# Nudge.net
KiCad netlist of a schematic drawn in EasyEDA Pro
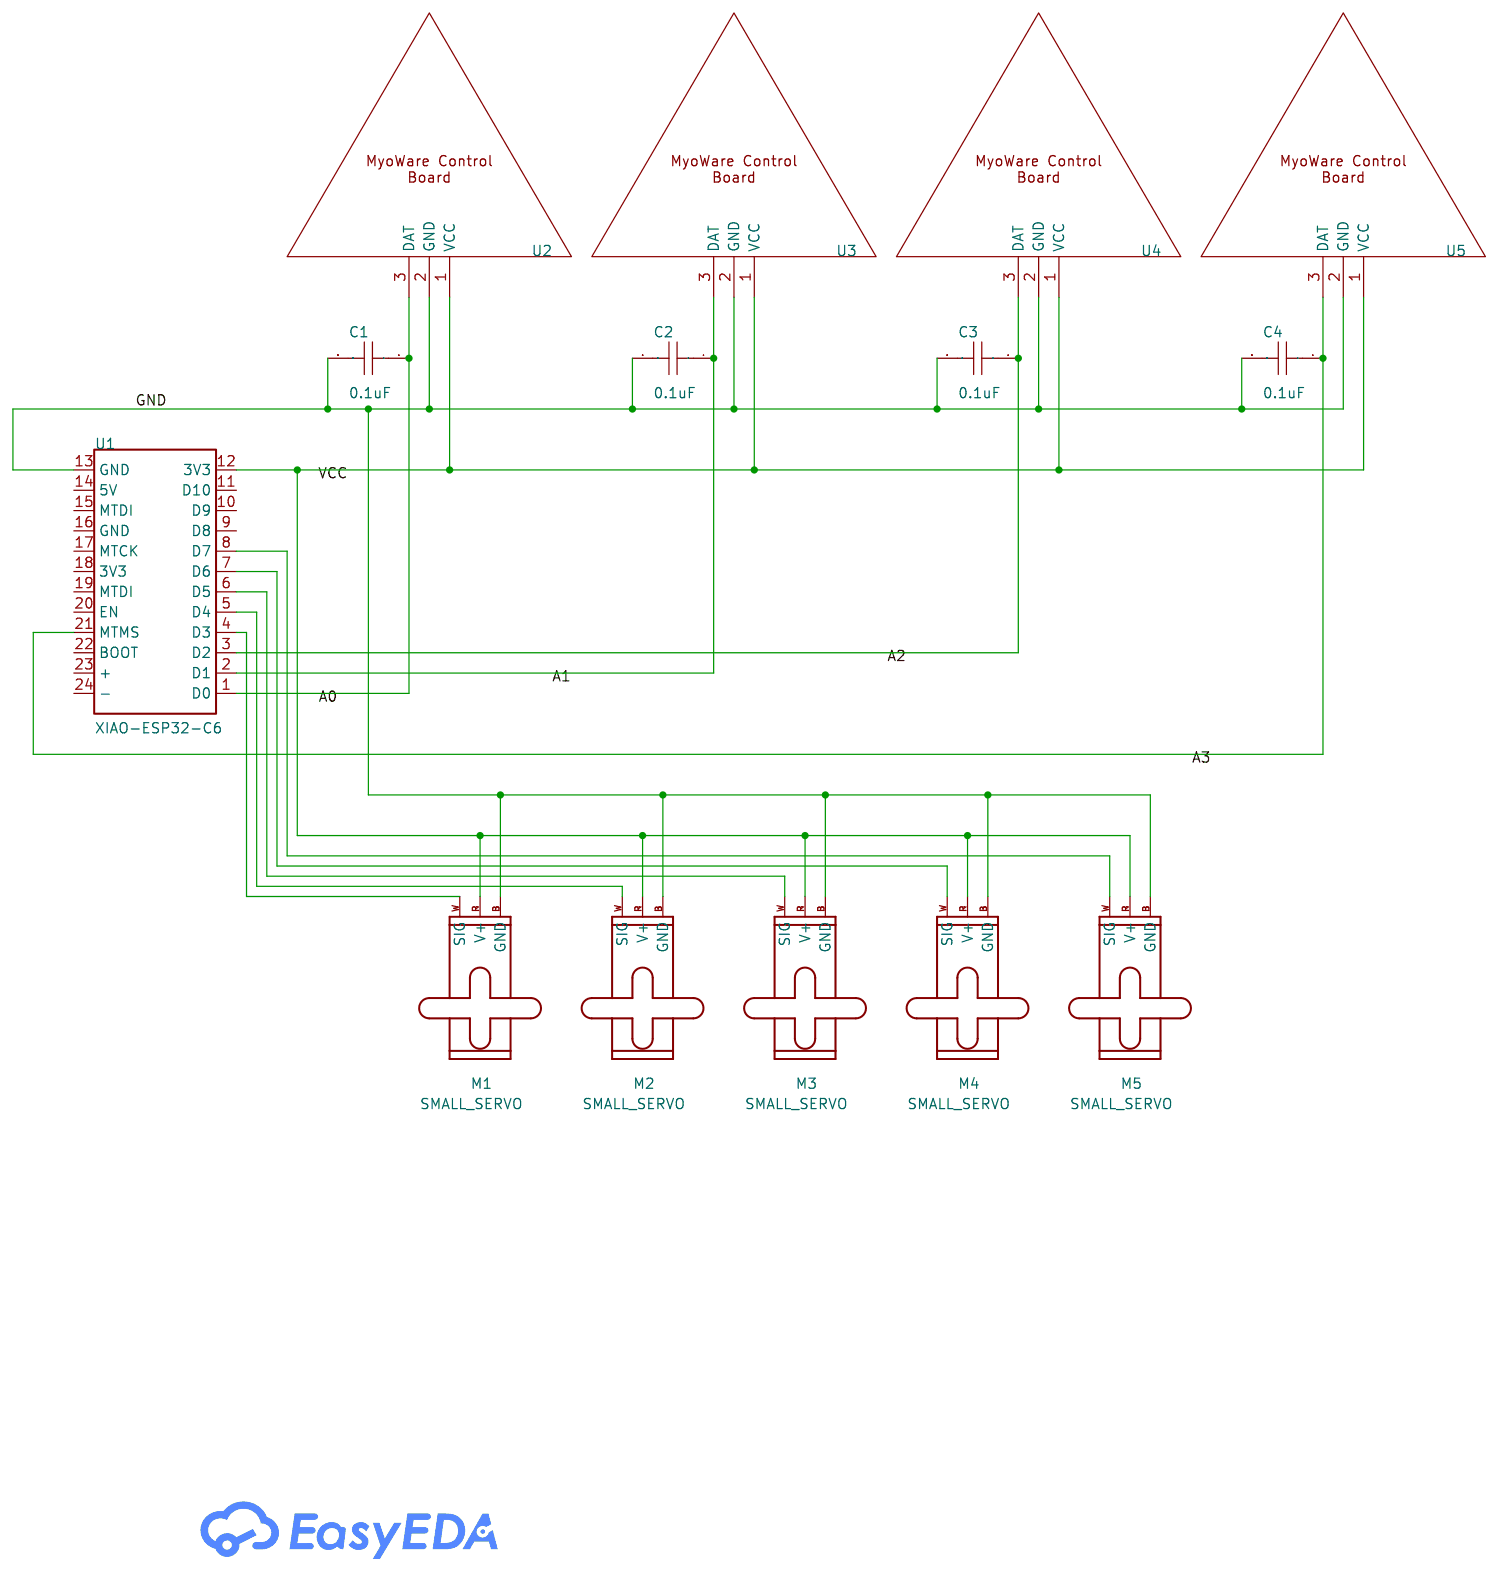
[diagram p0: schematic sheet]

(export (version "E")
  (design (tool "Eeschema 10.0.6"))
  (components
    (comp (ref "C1")
      (value "0.1uF")
      (footprint "easyedapro:C0603")
      (libsource (lib "easyedapro") (part "CapAcitance"))
    )
    (comp (ref "C2")
      (value "0.1uF")
      (footprint "easyedapro:C0603")
      (libsource (lib "easyedapro") (part "CapAcitance"))
    )
    (comp (ref "C3")
      (value "0.1uF")
      (footprint "easyedapro:C0603")
      (libsource (lib "easyedapro") (part "CapAcitance"))
    )
    (comp (ref "C4")
      (value "0.1uF")
      (footprint "easyedapro:C0603")
      (libsource (lib "easyedapro") (part "CapAcitance"))
    )
    (comp (ref "M1") (value "SMALL_SERVO") (libsource (lib "easyedapro") (part "SMALL_SERVO")))
    (comp (ref "M2") (value "SMALL_SERVO") (libsource (lib "easyedapro") (part "SMALL_SERVO")))
    (comp (ref "M3") (value "SMALL_SERVO") (libsource (lib "easyedapro") (part "SMALL_SERVO")))
    (comp (ref "M4") (value "SMALL_SERVO") (libsource (lib "easyedapro") (part "SMALL_SERVO")))
    (comp (ref "M5") (value "SMALL_SERVO") (libsource (lib "easyedapro") (part "SMALL_SERVO")))
    (comp (ref "U1") (value "XIAO-ESP32-C6") (libsource (lib "easyedapro") (part "XIAO-ESP32-C6")))
    (comp (ref "U2") (value "~") (libsource (lib "easyedapro") (part "MyoWare Board")))
    (comp (ref "U3") (value "~") (libsource (lib "easyedapro") (part "MyoWare Board")))
    (comp (ref "U4") (value "~") (libsource (lib "easyedapro") (part "MyoWare Board")))
    (comp (ref "U5") (value "~") (libsource (lib "easyedapro") (part "MyoWare Board")))
  )
  (nets
    (net (code "1") (name "/A0") (class "Default")
      (node (ref "C1") (pin "1") (pinfunction "1_1") (pintype "input"))
      (node (ref "U1") (pin "1") (pinfunction "D0_1") (pintype "unspecified"))
      (node (ref "U2") (pin "3") (pinfunction "DAT_3") (pintype "input"))
    )
    (net (code "2") (name "/A1") (class "Default")
      (node (ref "C2") (pin "1") (pinfunction "1_1") (pintype "input"))
      (node (ref "U1") (pin "2") (pinfunction "D1_2") (pintype "unspecified"))
      (node (ref "U3") (pin "3") (pinfunction "DAT_3") (pintype "input"))
    )
    (net (code "3") (name "/A2") (class "Default")
      (node (ref "C3") (pin "1") (pinfunction "1_1") (pintype "input"))
      (node (ref "U1") (pin "3") (pinfunction "D2_3") (pintype "unspecified"))
      (node (ref "U4") (pin "3") (pinfunction "DAT_3") (pintype "input"))
    )
    (net (code "4") (name "/A3") (class "Default")
      (node (ref "C4") (pin "1") (pinfunction "1_1") (pintype "input"))
      (node (ref "U1") (pin "21") (pinfunction "MTMS_21") (pintype "unspecified"))
      (node (ref "U5") (pin "3") (pinfunction "DAT_3") (pintype "input"))
    )
    (net (code "5") (name "/GND") (class "Default")
      (node (ref "C1") (pin "2") (pinfunction "2_2") (pintype "input"))
      (node (ref "C2") (pin "2") (pinfunction "2_2") (pintype "input"))
      (node (ref "C3") (pin "2") (pinfunction "2_2") (pintype "input"))
      (node (ref "C4") (pin "2") (pinfunction "2_2") (pintype "input"))
      (node (ref "M1") (pin "3") (pinfunction "GND_3") (pintype "unspecified"))
      (node (ref "M2") (pin "3") (pinfunction "GND_3") (pintype "unspecified"))
      (node (ref "M3") (pin "3") (pinfunction "GND_3") (pintype "unspecified"))
      (node (ref "M4") (pin "3") (pinfunction "GND_3") (pintype "unspecified"))
      (node (ref "M5") (pin "3") (pinfunction "GND_3") (pintype "unspecified"))
      (node (ref "U1") (pin "13") (pinfunction "GND_13") (pintype "unspecified"))
      (node (ref "U2") (pin "2") (pinfunction "GND_2") (pintype "input"))
      (node (ref "U3") (pin "2") (pinfunction "GND_2") (pintype "input"))
      (node (ref "U4") (pin "2") (pinfunction "GND_2") (pintype "input"))
      (node (ref "U5") (pin "2") (pinfunction "GND_2") (pintype "input"))
    )
    (net (code "6") (name "/VCC") (class "Default")
      (node (ref "M1") (pin "2") (pinfunction "V+_2") (pintype "unspecified"))
      (node (ref "M2") (pin "2") (pinfunction "V+_2") (pintype "unspecified"))
      (node (ref "M3") (pin "2") (pinfunction "V+_2") (pintype "unspecified"))
      (node (ref "M4") (pin "2") (pinfunction "V+_2") (pintype "unspecified"))
      (node (ref "M5") (pin "2") (pinfunction "V+_2") (pintype "unspecified"))
      (node (ref "U1") (pin "12") (pinfunction "3V3_12") (pintype "unspecified"))
      (node (ref "U2") (pin "1") (pinfunction "VCC_1") (pintype "input"))
      (node (ref "U3") (pin "1") (pinfunction "VCC_1") (pintype "input"))
      (node (ref "U4") (pin "1") (pinfunction "VCC_1") (pintype "input"))
      (node (ref "U5") (pin "1") (pinfunction "VCC_1") (pintype "input"))
    )
    (net (code "7") (name "Net-(M1-SIG)") (class "Default")
      (node (ref "M1") (pin "1") (pinfunction "SIG_1") (pintype "unspecified"))
      (node (ref "U1") (pin "4") (pinfunction "D3_4") (pintype "unspecified"))
    )
    (net (code "8") (name "Net-(M2-SIG)") (class "Default")
      (node (ref "M2") (pin "1") (pinfunction "SIG_1") (pintype "unspecified"))
      (node (ref "U1") (pin "5") (pinfunction "D4_5") (pintype "unspecified"))
    )
    (net (code "9") (name "Net-(M3-SIG)") (class "Default")
      (node (ref "M3") (pin "1") (pinfunction "SIG_1") (pintype "unspecified"))
      (node (ref "U1") (pin "6") (pinfunction "D5_6") (pintype "unspecified"))
    )
    (net (code "10") (name "Net-(M4-SIG)") (class "Default")
      (node (ref "M4") (pin "1") (pinfunction "SIG_1") (pintype "unspecified"))
      (node (ref "U1") (pin "7") (pinfunction "D6_7") (pintype "unspecified"))
    )
    (net (code "11") (name "Net-(M5-SIG)") (class "Default")
      (node (ref "M5") (pin "1") (pinfunction "SIG_1") (pintype "unspecified"))
      (node (ref "U1") (pin "8") (pinfunction "D7_8") (pintype "unspecified"))
    )
    (net (code "12") (name "unconnected-(U1-+-Pad23)") (class "Default")
      (node (ref "U1") (pin "23") (pinfunction "+_23") (pintype "unspecified"))
    )
    (net (code "13") (name "unconnected-(U1---Pad24)") (class "Default")
      (node (ref "U1") (pin "24") (pinfunction "-_24") (pintype "unspecified"))
    )
    (net (code "14") (name "unconnected-(U1-3V3-Pad18)") (class "Default")
      (node (ref "U1") (pin "18") (pinfunction "3V3_18") (pintype "unspecified"))
    )
    (net (code "15") (name "unconnected-(U1-5V-Pad14)") (class "Default")
      (node (ref "U1") (pin "14") (pinfunction "5V_14") (pintype "unspecified"))
    )
    (net (code "16") (name "unconnected-(U1-BOOT-Pad22)") (class "Default")
      (node (ref "U1") (pin "22") (pinfunction "BOOT_22") (pintype "unspecified"))
    )
    (net (code "17") (name "unconnected-(U1-D8-Pad9)") (class "Default")
      (node (ref "U1") (pin "9") (pinfunction "D8_9") (pintype "unspecified"))
    )
    (net (code "18") (name "unconnected-(U1-D9-Pad10)") (class "Default")
      (node (ref "U1") (pin "10") (pinfunction "D9_10") (pintype "unspecified"))
    )
    (net (code "19") (name "unconnected-(U1-D10-Pad11)") (class "Default")
      (node (ref "U1") (pin "11") (pinfunction "D10_11") (pintype "unspecified"))
    )
    (net (code "20") (name "unconnected-(U1-EN-Pad20)") (class "Default")
      (node (ref "U1") (pin "20") (pinfunction "EN_20") (pintype "unspecified"))
    )
    (net (code "21") (name "unconnected-(U1-GND-Pad16)") (class "Default")
      (node (ref "U1") (pin "16") (pinfunction "GND_16") (pintype "unspecified"))
    )
    (net (code "22") (name "unconnected-(U1-MTCK-Pad17)") (class "Default")
      (node (ref "U1") (pin "17") (pinfunction "MTCK_17") (pintype "unspecified"))
    )
    (net (code "23") (name "unconnected-(U1-MTDI-Pad15)") (class "Default")
      (node (ref "U1") (pin "15") (pinfunction "MTDI_15") (pintype "unspecified"))
    )
    (net (code "24") (name "unconnected-(U1-MTDI-Pad19)") (class "Default")
      (node (ref "U1") (pin "19") (pinfunction "MTDI_19") (pintype "unspecified"))
    )
  )
)
